# Grove_-_RTC_v1_1.net
KiCad netlist of a schematic drawn in EAGLE
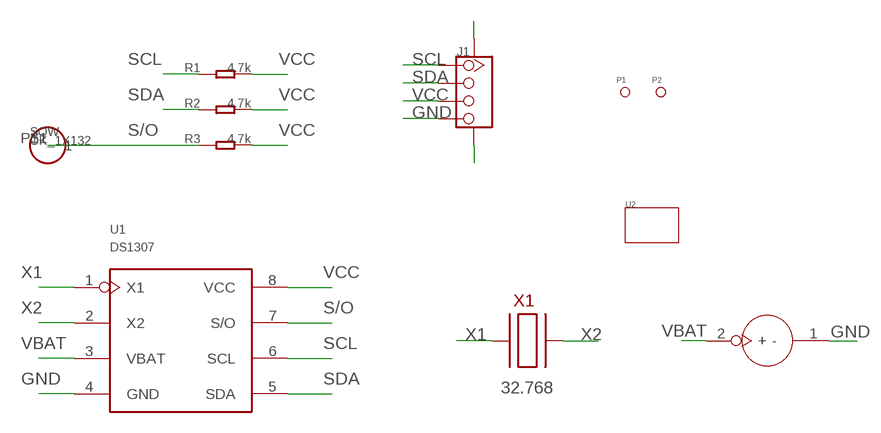
[diagram p0: schematic, sheet 1]

(export (version "E")
  (design (tool "Eeschema 10.0.6"))
  (components
    (comp (ref "J1")
      (value "TWIG-4P-2.0-SMD-FEMALE-REINFORCE'DD'")
      (footprint "eagle-import:4P-SMD-2.0")
      (libsource (lib "eagle-import") (part "TWIG-4P-2.0-SMD-FEMALE-REINFORCE'DD'"))
    )
    (comp (ref "P1")
      (value "PAD-MARK")
      (footprint "eagle-import:ROUND-MARK-1.0")
      (fields (field (name "PARTNO") "DNP"))
      (libsource (lib "eagle-import") (part "PAD-MARK"))
    )
    (comp (ref "P2")
      (value "PAD-MARK")
      (footprint "eagle-import:ROUND-MARK-1.0")
      (fields (field (name "PARTNO") "DNP"))
      (libsource (lib "eagle-import") (part "PAD-MARK"))
    )
    (comp (ref "R1")
      (value "4.7k")
      (footprint "eagle-import:0603")
      (libsource (lib "eagle-import") (part "R0603"))
    )
    (comp (ref "R2")
      (value "4.7k")
      (footprint "eagle-import:0603")
      (libsource (lib "eagle-import") (part "R0603"))
    )
    (comp (ref "R3")
      (value "4.7k")
      (footprint "eagle-import:0603")
      (libsource (lib "eagle-import") (part "R0603"))
    )
    (comp (ref "SQW")
      (value "CK_1X132")
      (footprint "eagle-import:CK_1X1")
      (libsource (lib "eagle-import") (part "CK_1X132"))
    )
    (comp (ref "U1")
      (value "DS1307")
      (footprint "eagle-import:SO08")
      (libsource (lib "eagle-import") (part "DS1307"))
    )
    (comp (ref "U2")
      (value "TWIG-2U")
      (footprint "eagle-import:2U-DIM-W_-DRILL")
      (libsource (lib "eagle-import") (part "TWIG-2U"))
    )
    (comp (ref "U3")
      (value "BATTERYBATTERY1225_SMT")
      (footprint "eagle-import:BATTERY1225_SMT")
      (libsource (lib "eagle-import") (part "BATTERYBATTERY1225_SMT"))
    )
    (comp (ref "X1")
      (value "XTL_S")
      (footprint "eagle-import:XTL_S")
      (libsource (lib "eagle-import") (part "XTL_S"))
    )
  )
  (nets
    (net (code "1") (name "/GND") (class "Default")
      (node (ref "J1") (pin "4") (pinfunction "4_4") (pintype "bidirectional"))
      (node (ref "J1") (pin "SS1") (pinfunction "SS1_SS1") (pintype "bidirectional"))
      (node (ref "J1") (pin "SS2") (pinfunction "SS2_SS2") (pintype "bidirectional"))
      (node (ref "U1") (pin "4") (pinfunction "GND_4") (pintype "bidirectional"))
      (node (ref "U3") (pin "1") (pinfunction "-_1") (pintype "bidirectional"))
    )
    (net (code "2") (name "/SCL") (class "Default")
      (node (ref "J1") (pin "1") (pinfunction "1_1") (pintype "bidirectional"))
      (node (ref "R1") (pin "1") (pinfunction "1_1") (pintype "bidirectional"))
      (node (ref "U1") (pin "6") (pinfunction "SCL_6") (pintype "bidirectional"))
    )
    (net (code "3") (name "/SDA") (class "Default")
      (node (ref "J1") (pin "2") (pinfunction "2_2") (pintype "bidirectional"))
      (node (ref "R2") (pin "1") (pinfunction "1_1") (pintype "bidirectional"))
      (node (ref "U1") (pin "5") (pinfunction "SDA_5") (pintype "bidirectional"))
    )
    (net (code "4") (name "/S{slash}O") (class "Default")
      (node (ref "R3") (pin "1") (pinfunction "1_1") (pintype "bidirectional"))
      (node (ref "SQW") (pin "P$1") (pinfunction "1_P$1") (pintype "bidirectional"))
      (node (ref "U1") (pin "7") (pinfunction "S/O_7") (pintype "bidirectional"))
    )
    (net (code "5") (name "/VBAT") (class "Default")
      (node (ref "U1") (pin "3") (pinfunction "VBAT_3") (pintype "bidirectional"))
      (node (ref "U3") (pin "2") (pinfunction "+_2") (pintype "bidirectional"))
    )
    (net (code "6") (name "/VCC") (class "Default")
      (node (ref "J1") (pin "3") (pinfunction "3_3") (pintype "bidirectional"))
      (node (ref "R1") (pin "2") (pinfunction "2_2") (pintype "bidirectional"))
      (node (ref "R2") (pin "2") (pinfunction "2_2") (pintype "bidirectional"))
      (node (ref "R3") (pin "2") (pinfunction "2_2") (pintype "bidirectional"))
      (node (ref "U1") (pin "8") (pinfunction "VCC_8") (pintype "bidirectional"))
    )
    (net (code "7") (name "/X1") (class "Default")
      (node (ref "U1") (pin "1") (pinfunction "X1_1") (pintype "bidirectional"))
      (node (ref "X1") (pin "1") (pinfunction "P$1_1") (pintype "bidirectional"))
    )
    (net (code "8") (name "/X2") (class "Default")
      (node (ref "U1") (pin "2") (pinfunction "X2_2") (pintype "bidirectional"))
      (node (ref "X1") (pin "2") (pinfunction "P$2_2") (pintype "bidirectional"))
    )
  )
)
